# stm32_schematic.net
KiCad netlist of a schematic drawn in Altium Designer
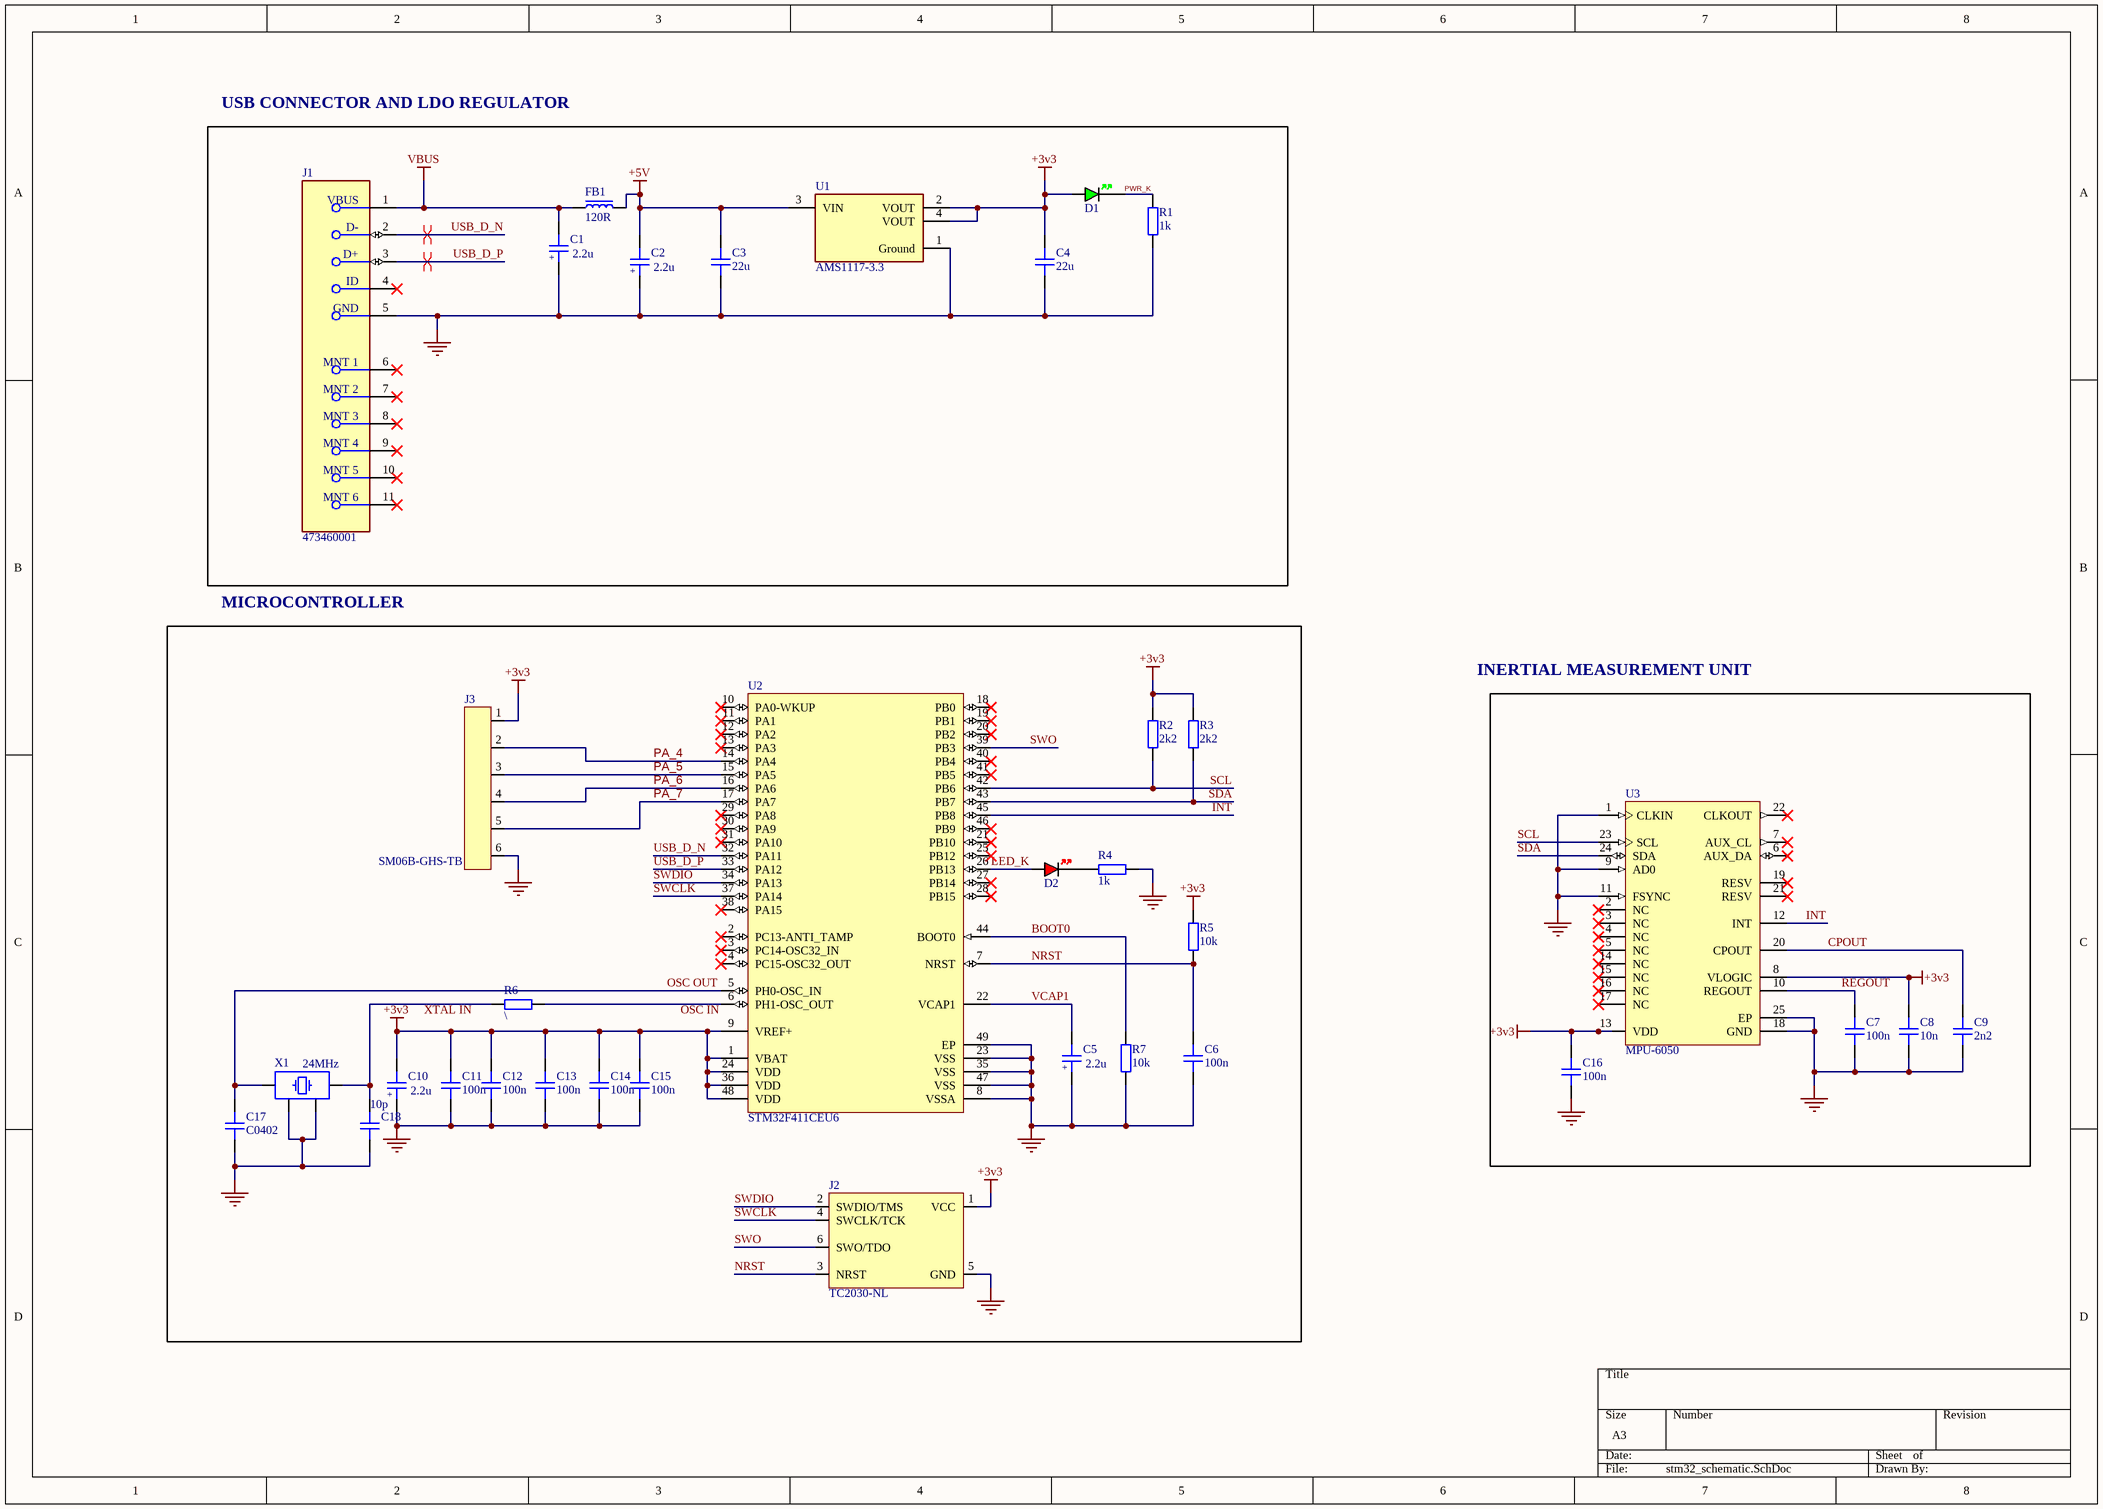
[diagram p0: stm32_schematic.SchDoc]

(export (version "E")
  (design (tool "Eeschema 10.0.6"))
  (components
    (comp (ref "C1")
      (value "2.2u")
      (footprint "CAP_TANT_0603")
      (description "Capacitor SMD Tantalum 0603")
      (libsource (lib "Schematic-Lib-PhilsLab") (part "CAP_TANT_0603"))
    )
    (comp (ref "C2")
      (value "2.2u")
      (footprint "CAP_TANT_0603")
      (description "Capacitor SMD Tantalum 0603")
      (libsource (lib "Schematic-Lib-PhilsLab") (part "CAP_TANT_0603"))
    )
    (comp (ref "C3")
      (value "22u")
      (footprint "CAP_0805")
      (description "Capacitor SMD 0805")
      (libsource (lib "Schematic-Lib-PhilsLab") (part "CAP_0805"))
    )
    (comp (ref "C4")
      (value "22u")
      (footprint "CAP_0805")
      (description "Capacitor SMD 0805")
      (libsource (lib "Schematic-Lib-PhilsLab") (part "CAP_0805"))
    )
    (comp (ref "C5")
      (value "2.2u")
      (footprint "CAP_TANT_0603")
      (description "Capacitor SMD Tantalum 0603")
      (libsource (lib "Schematic-Lib-PhilsLab") (part "CAP_TANT_0603"))
    )
    (comp (ref "C6")
      (value "100n")
      (footprint "CAP_0402")
      (description "Capacitor SMD 0402")
      (libsource (lib "Schematic-Lib-PhilsLab") (part "CAP_0402"))
    )
    (comp (ref "C7")
      (value "100n")
      (footprint "CAP_0402")
      (description "Capacitor SMD 0402")
      (libsource (lib "Schematic-Lib-PhilsLab") (part "CAP_0402"))
    )
    (comp (ref "C8")
      (value "10n")
      (footprint "CAP_0402")
      (description "Capacitor SMD 0402")
      (libsource (lib "Schematic-Lib-PhilsLab") (part "CAP_0402"))
    )
    (comp (ref "C9")
      (value "2n2")
      (footprint "CAP_0402")
      (description "Capacitor SMD 0402")
      (libsource (lib "Schematic-Lib-PhilsLab") (part "CAP_0402"))
    )
    (comp (ref "C10")
      (value "2.2u")
      (footprint "CAP_TANT_0603")
      (description "Capacitor SMD Tantalum 0603")
      (libsource (lib "Schematic-Lib-PhilsLab") (part "CAP_TANT_0603"))
    )
    (comp (ref "C11")
      (value "100n")
      (footprint "CAP_0402")
      (description "Capacitor SMD 0402")
      (libsource (lib "Schematic-Lib-PhilsLab") (part "CAP_0402"))
    )
    (comp (ref "C12")
      (value "100n")
      (footprint "CAP_0402")
      (description "Capacitor SMD 0402")
      (libsource (lib "Schematic-Lib-PhilsLab") (part "CAP_0402"))
    )
    (comp (ref "C13")
      (value "100n")
      (footprint "CAP_0402")
      (description "Capacitor SMD 0402")
      (libsource (lib "Schematic-Lib-PhilsLab") (part "CAP_0402"))
    )
    (comp (ref "C14")
      (value "100n")
      (footprint "CAP_0402")
      (description "Capacitor SMD 0402")
      (libsource (lib "Schematic-Lib-PhilsLab") (part "CAP_0402"))
    )
    (comp (ref "C15")
      (value "100n")
      (footprint "CAP_0402")
      (description "Capacitor SMD 0402")
      (libsource (lib "Schematic-Lib-PhilsLab") (part "CAP_0402"))
    )
    (comp (ref "C16")
      (value "100n")
      (footprint "CAP_0402")
      (description "Capacitor SMD 0402")
      (libsource (lib "Schematic-Lib-PhilsLab") (part "CAP_0402"))
    )
    (comp (ref "C17")
      (value "C0402")
      (footprint "CAP_0402")
      (description "Capacitor SMD 0402")
      (libsource (lib "Schematic-Lib-PhilsLab") (part "CAP_0402"))
    )
    (comp (ref "C18")
      (value "10p")
      (footprint "CAP_0402")
      (description "Capacitor SMD 0402")
      (libsource (lib "Schematic-Lib-PhilsLab") (part "CAP_0402"))
    )
    (comp (ref "D1")
      (value "GREEN")
      (footprint "LED_0402_GREEN")
      (description "LED 0402 GREEN SMD")
      (libsource (lib "Schematic-Lib-PhilsLab") (part "LED_0402_GREEN"))
    )
    (comp (ref "D2")
      (value "RED")
      (footprint "LED_0402_RED")
      (description "LED 0402 RED SMD")
      (libsource (lib "Schematic-Lib-PhilsLab") (part "LED_0402_RED"))
    )
    (comp (ref "FB1")
      (value "120R")
      (footprint "FB_0603")
      (description "Ferrite Bead SMD 0603")
      (libsource (lib "Schematic-Lib-PhilsLab") (part "FB_0603"))
    )
    (comp (ref "J1")
      (value "473460001")
      (footprint "FP-473460001-MFG")
      (description "CONN RCPT USB2.0 MICRO B SMD R/A")
      (fields
        (field (name "OCTOPART") "https://octopart.com/47346-0001-molex-7164928")
        (field (name "MANUFACTURER") "Molex")
      )
      (libsource (lib "Altium Content Vault") (part "53ae1f1d9b557310b43ca686e5bb76a"))
    )
    (comp (ref "J2")
      (value "TC2030-NL")
      (footprint "TC2030-NL-FP")
      (description "Tag-Connect No-Solder SWD Debug Connector (No Legs) DO NOT PLACE")
      (fields
        (field (name "MANUFACTURER") "Tag-Connect")
        (field (name "MANUFACTURER PART NUMBER") "TC2030-NL-FP")
      )
      (libsource (lib "Schematic-Lib-PhilsLab") (part "TC2030-NL"))
    )
    (comp (ref "J3")
      (value "SM06B-GHS-TB")
      (footprint "SM06B-GHS-TB")
      (description "Header Connector 6 Position 1.25MM Pitch SMD Horizontal JST GH")
      (fields (field (name "MANUFACTURER") "JST"))
      (libsource (lib "Schematic-Lib-PhilsLab") (part "SM06B-GHS-TB"))
    )
    (comp (ref "R1")
      (value "1k")
      (footprint "RES_0402")
      (description "Resistor SMD 0402")
      (libsource (lib "Schematic-Lib-PhilsLab") (part "RES_0402"))
    )
    (comp (ref "R2")
      (value "2k2")
      (footprint "RES_0402")
      (description "Resistor SMD 0402")
      (libsource (lib "Schematic-Lib-PhilsLab") (part "RES_0402"))
    )
    (comp (ref "R3")
      (value "2k2")
      (footprint "RES_0402")
      (description "Resistor SMD 0402")
      (libsource (lib "Schematic-Lib-PhilsLab") (part "RES_0402"))
    )
    (comp (ref "R4")
      (value "1k")
      (footprint "RES_0402")
      (description "Resistor SMD 0402")
      (libsource (lib "Schematic-Lib-PhilsLab") (part "RES_0402"))
    )
    (comp (ref "R5")
      (value "10k")
      (footprint "RES_0402")
      (description "Resistor SMD 0402")
      (libsource (lib "Schematic-Lib-PhilsLab") (part "RES_0402"))
    )
    (comp (ref "R6")
      (value "\\")
      (footprint "RES_0402")
      (description "Resistor SMD 0402")
      (libsource (lib "Schematic-Lib-PhilsLab") (part "RES_0402"))
    )
    (comp (ref "R7")
      (value "10k")
      (footprint "RES_0402")
      (description "Resistor SMD 0402")
      (libsource (lib "Schematic-Lib-PhilsLab") (part "RES_0402"))
    )
    (comp (ref "U1")
      (value "AMS1117-3.3")
      (footprint "FP-AMS1117-IPC_C")
      (description "LDO Voltage Regulators 1A, 3.3V")
      (fields
        (field (name "OCTOPART") "https://octopart.com/ams1117-3.3-advanced+monolithic+systems-25899300")
        (field (name "MANUFACTURER") "Advanced Monolithic Systems")
      )
      (libsource (lib "Altium Content Vault") (part "8bdbb5f8e77002000e30dd2845d0354"))
    )
    (comp (ref "U2")
      (value "STM32F411CEU6")
      (footprint "STM-UFQFPN48_L")
      (libsource (lib "Altium Content Vault") (part "MC-ARM-STM32F411-UFQFPN48"))
    )
    (comp (ref "U3")
      (value "MPU-6050")
      (footprint "IS-QFN-24_V")
      (fields (field (name "MANUFACTURER") "InvenSense"))
      (libsource (lib "Altium Content Vault") (part "IS-MPU-6050-QFN-24"))
    )
    (comp (ref "X1")
      (value "24MHz")
      (footprint "XTAL_3225")
      (description "Crystal SMD 24MHz 10PPM 7pF 3225")
      (fields
        (field (name "MANUFACTURER") "Epson")
        (field (name "MANUFACTURER PART NUMBER") "TSX-3225 24.0000MF15X-AC")
      )
      (libsource (lib "Schematic-Lib-PhilsLab") (part "TSX-3225_24.0000MF15X-AC"))
    )
  )
  (nets
    (net (code "1") (name "+3v3") (class "Default")
      (node (ref "C10") (pin "K") (pinfunction "K_K") (pintype "passive"))
      (node (ref "C11") (pin "2") (pinfunction "2_2") (pintype "passive"))
      (node (ref "C12") (pin "2") (pinfunction "2_2") (pintype "passive"))
      (node (ref "C13") (pin "2") (pinfunction "2_2") (pintype "passive"))
      (node (ref "C14") (pin "2") (pinfunction "2_2") (pintype "passive"))
      (node (ref "C15") (pin "2") (pinfunction "2_2") (pintype "passive"))
      (node (ref "C16") (pin "2") (pinfunction "2_2") (pintype "passive"))
      (node (ref "C4") (pin "2") (pinfunction "2_2") (pintype "passive"))
      (node (ref "C8") (pin "1") (pinfunction "1_1") (pintype "passive"))
      (node (ref "D1") (pin "A") (pinfunction "A_A") (pintype "passive"))
      (node (ref "J2") (pin "1") (pinfunction "VCC_1") (pintype "passive"))
      (node (ref "J3") (pin "1") (pinfunction "1_1") (pintype "passive"))
      (node (ref "R2") (pin "2") (pinfunction "2_2") (pintype "passive"))
      (node (ref "R3") (pin "2") (pinfunction "2_2") (pintype "passive"))
      (node (ref "R5") (pin "2") (pinfunction "2_2") (pintype "passive"))
      (node (ref "U1") (pin "2") (pinfunction "VOUT_2") (pintype "passive"))
      (node (ref "U1") (pin "4") (pinfunction "VOUT_4") (pintype "passive"))
      (node (ref "U2") (pin "1") (pinfunction "VBAT_1") (pintype "power_in"))
      (node (ref "U2") (pin "24") (pinfunction "VDD_24") (pintype "power_in"))
      (node (ref "U2") (pin "36") (pinfunction "VDD_36") (pintype "power_in"))
      (node (ref "U2") (pin "48") (pinfunction "VDD_48") (pintype "power_in"))
      (node (ref "U2") (pin "9") (pinfunction "VREF+_9") (pintype "power_in"))
      (node (ref "U3") (pin "13") (pinfunction "VDD_13") (pintype "power_in"))
      (node (ref "U3") (pin "8") (pinfunction "VLOGIC_8") (pintype "power_in"))
    )
    (net (code "2") (name "+5V") (class "Default")
      (node (ref "C2") (pin "K") (pinfunction "K_K") (pintype "passive"))
      (node (ref "C3") (pin "2") (pinfunction "2_2") (pintype "passive"))
      (node (ref "FB1") (pin "2") (pinfunction "2_2") (pintype "passive"))
      (node (ref "U1") (pin "3") (pinfunction "VIN_3") (pintype "power_in"))
    )
    (net (code "3") (name "/BOOT0") (class "Default")
      (node (ref "R7") (pin "2") (pinfunction "2_2") (pintype "passive"))
      (node (ref "U2") (pin "44") (pinfunction "BOOT0_44") (pintype "input"))
    )
    (net (code "4") (name "/CPOUT") (class "Default")
      (node (ref "C9") (pin "1") (pinfunction "1_1") (pintype "passive"))
      (node (ref "U3") (pin "20") (pinfunction "CPOUT_20") (pintype "passive"))
    )
    (net (code "5") (name "/INT") (class "Default")
      (node (ref "U2") (pin "45") (pinfunction "PB8_45") (pintype "bidirectional"))
      (node (ref "U3") (pin "12") (pinfunction "INT_12") (pintype "open_collector"))
    )
    (net (code "6") (name "/LED_K") (class "Default")
      (node (ref "D2") (pin "A") (pinfunction "A_A") (pintype "passive"))
      (node (ref "U2") (pin "26") (pinfunction "PB13_26") (pintype "bidirectional"))
    )
    (net (code "7") (name "/NRST") (class "Default")
      (node (ref "C6") (pin "2") (pinfunction "2_2") (pintype "passive"))
      (node (ref "J2") (pin "3") (pinfunction "NRST_3") (pintype "passive"))
      (node (ref "R5") (pin "1") (pinfunction "1_1") (pintype "passive"))
      (node (ref "U2") (pin "7") (pinfunction "NRST_7") (pintype "bidirectional"))
    )
    (net (code "9") (name "/OSC OUT") (class "Default")
      (node (ref "C17") (pin "2") (pinfunction "2_2") (pintype "passive"))
      (node (ref "U2") (pin "5") (pinfunction "PH0-OSC_IN_5") (pintype "bidirectional"))
      (node (ref "X1") (pin "1") (pinfunction "1_1") (pintype "passive"))
    )
    (net (code "10") (name "/PA_4") (class "Default")
      (node (ref "J3") (pin "2") (pinfunction "2_2") (pintype "passive"))
      (node (ref "U2") (pin "14") (pinfunction "PA4_14") (pintype "bidirectional"))
    )
    (net (code "11") (name "/PA_5") (class "Default")
      (node (ref "J3") (pin "3") (pinfunction "3_3") (pintype "passive"))
      (node (ref "U2") (pin "15") (pinfunction "PA5_15") (pintype "bidirectional"))
    )
    (net (code "12") (name "/PA_6") (class "Default")
      (node (ref "J3") (pin "4") (pinfunction "4_4") (pintype "passive"))
      (node (ref "U2") (pin "16") (pinfunction "PA6_16") (pintype "bidirectional"))
    )
    (net (code "13") (name "/PA_7") (class "Default")
      (node (ref "J3") (pin "5") (pinfunction "5_5") (pintype "passive"))
      (node (ref "U2") (pin "17") (pinfunction "PA7_17") (pintype "bidirectional"))
    )
    (net (code "14") (name "/PWR_K") (class "Default")
      (node (ref "D1") (pin "K") (pinfunction "K_K") (pintype "passive"))
      (node (ref "R1") (pin "2") (pinfunction "2_2") (pintype "passive"))
    )
    (net (code "15") (name "/REGOUT") (class "Default")
      (node (ref "C7") (pin "1") (pinfunction "1_1") (pintype "passive"))
      (node (ref "U3") (pin "10") (pinfunction "REGOUT_10") (pintype "passive"))
    )
    (net (code "16") (name "/SCL") (class "Default")
      (node (ref "R2") (pin "1") (pinfunction "1_1") (pintype "passive"))
      (node (ref "U2") (pin "42") (pinfunction "PB6_42") (pintype "bidirectional"))
      (node (ref "U3") (pin "23") (pinfunction "SCL_23") (pintype "input"))
    )
    (net (code "17") (name "/SDA") (class "Default")
      (node (ref "R3") (pin "1") (pinfunction "1_1") (pintype "passive"))
      (node (ref "U2") (pin "43") (pinfunction "PB7_43") (pintype "bidirectional"))
      (node (ref "U3") (pin "24") (pinfunction "SDA_24") (pintype "bidirectional"))
    )
    (net (code "18") (name "/SWCLK") (class "Default")
      (node (ref "J2") (pin "4") (pinfunction "SWCLK/TCK_4") (pintype "passive"))
      (node (ref "U2") (pin "37") (pinfunction "PA14_37") (pintype "bidirectional"))
    )
    (net (code "19") (name "/SWDIO") (class "Default")
      (node (ref "J2") (pin "2") (pinfunction "SWDIO/TMS_2") (pintype "passive"))
      (node (ref "U2") (pin "34") (pinfunction "PA13_34") (pintype "bidirectional"))
    )
    (net (code "20") (name "/SWO") (class "Default")
      (node (ref "J2") (pin "6") (pinfunction "SWO/TDO_6") (pintype "passive"))
      (node (ref "U2") (pin "39") (pinfunction "PB3_39") (pintype "bidirectional"))
    )
    (net (code "21") (name "/USB_D_N") (class "Default")
      (node (ref "J1") (pin "2") (pinfunction "D-_2") (pintype "bidirectional"))
      (node (ref "U2") (pin "32") (pinfunction "PA11_32") (pintype "bidirectional"))
    )
    (net (code "22") (name "/USB_D_P") (class "Default")
      (node (ref "J1") (pin "3") (pinfunction "D+_3") (pintype "bidirectional"))
      (node (ref "U2") (pin "33") (pinfunction "PA12_33") (pintype "bidirectional"))
    )
    (net (code "23") (name "/VCAP1") (class "Default")
      (node (ref "C5") (pin "K") (pinfunction "K_K") (pintype "passive"))
      (node (ref "U2") (pin "22") (pinfunction "VCAP1_22") (pintype "passive"))
    )
    (net (code "25") (name "GND") (class "Default")
      (node (ref "C1") (pin "A") (pinfunction "A_A") (pintype "passive"))
      (node (ref "C10") (pin "A") (pinfunction "A_A") (pintype "passive"))
      (node (ref "C11") (pin "1") (pinfunction "1_1") (pintype "passive"))
      (node (ref "C12") (pin "1") (pinfunction "1_1") (pintype "passive"))
      (node (ref "C13") (pin "1") (pinfunction "1_1") (pintype "passive"))
      (node (ref "C14") (pin "1") (pinfunction "1_1") (pintype "passive"))
      (node (ref "C15") (pin "1") (pinfunction "1_1") (pintype "passive"))
      (node (ref "C16") (pin "1") (pinfunction "1_1") (pintype "passive"))
      (node (ref "C17") (pin "1") (pinfunction "1_1") (pintype "passive"))
      (node (ref "C18") (pin "1") (pinfunction "1_1") (pintype "passive"))
      (node (ref "C2") (pin "A") (pinfunction "A_A") (pintype "passive"))
      (node (ref "C3") (pin "1") (pinfunction "1_1") (pintype "passive"))
      (node (ref "C4") (pin "1") (pinfunction "1_1") (pintype "passive"))
      (node (ref "C5") (pin "A") (pinfunction "A_A") (pintype "passive"))
      (node (ref "C6") (pin "1") (pinfunction "1_1") (pintype "passive"))
      (node (ref "C7") (pin "2") (pinfunction "2_2") (pintype "passive"))
      (node (ref "C8") (pin "2") (pinfunction "2_2") (pintype "passive"))
      (node (ref "C9") (pin "2") (pinfunction "2_2") (pintype "passive"))
      (node (ref "J1") (pin "5") (pinfunction "GND_5") (pintype "power_in"))
      (node (ref "J2") (pin "5") (pinfunction "GND_5") (pintype "passive"))
      (node (ref "J3") (pin "6") (pinfunction "6_6") (pintype "passive"))
      (node (ref "R1") (pin "1") (pinfunction "1_1") (pintype "passive"))
      (node (ref "R4") (pin "1") (pinfunction "1_1") (pintype "passive"))
      (node (ref "R7") (pin "1") (pinfunction "1_1") (pintype "passive"))
      (node (ref "U1") (pin "1") (pinfunction "Ground_1") (pintype "power_in"))
      (node (ref "U2") (pin "23") (pinfunction "VSS_23") (pintype "power_in"))
      (node (ref "U2") (pin "35") (pinfunction "VSS_35") (pintype "power_in"))
      (node (ref "U2") (pin "47") (pinfunction "VSS_47") (pintype "power_in"))
      (node (ref "U2") (pin "49") (pinfunction "EP_49") (pintype "power_in"))
      (node (ref "U2") (pin "8") (pinfunction "VSSA_8") (pintype "power_in"))
      (node (ref "U3") (pin "1") (pinfunction "CLKIN_1") (pintype "input"))
      (node (ref "U3") (pin "11") (pinfunction "FSYNC_11") (pintype "input"))
      (node (ref "U3") (pin "18") (pinfunction "GND_18") (pintype "power_in"))
      (node (ref "U3") (pin "25") (pinfunction "EP_25") (pintype "power_in"))
      (node (ref "U3") (pin "9") (pinfunction "AD0_9") (pintype "input"))
      (node (ref "X1") (pin "2") (pinfunction "2_2") (pintype "passive"))
      (node (ref "X1") (pin "4") (pinfunction "4_4") (pintype "passive"))
    )
    (net (code "26") (name "Net-(C18-Pad2)") (class "Default")
      (node (ref "C18") (pin "2") (pinfunction "2_2") (pintype "passive"))
      (node (ref "R6") (pin "2") (pinfunction "2_2") (pintype "passive"))
      (node (ref "X1") (pin "3") (pinfunction "3_3") (pintype "passive"))
    )
    (net (code "27") (name "Net-(D2-PadK)") (class "Default")
      (node (ref "D2") (pin "K") (pinfunction "K_K") (pintype "passive"))
      (node (ref "R4") (pin "2") (pinfunction "2_2") (pintype "passive"))
    )
    (net (code "28") (name "Net-(U2-PH1-OSC_OUT)") (class "Default")
      (node (ref "R6") (pin "1") (pinfunction "1_1") (pintype "passive"))
      (node (ref "U2") (pin "6") (pinfunction "PH1-OSC_OUT_6") (pintype "bidirectional"))
    )
    (net (code "29") (name "VBUS") (class "Default")
      (node (ref "C1") (pin "K") (pinfunction "K_K") (pintype "passive"))
      (node (ref "FB1") (pin "1") (pinfunction "1_1") (pintype "passive"))
      (node (ref "J1") (pin "1") (pinfunction "VBUS_1") (pintype "power_in"))
    )
    (net (code "30") (name "unconnected-(J1-ID-Pad4)") (class "Default")
      (node (ref "J1") (pin "4") (pinfunction "ID_4") (pintype "passive+no_connect"))
    )
    (net (code "31") (name "unconnected-(J1-MNT_1-Pad6)") (class "Default")
      (node (ref "J1") (pin "6") (pinfunction "MNT_1_6") (pintype "passive+no_connect"))
    )
    (net (code "32") (name "unconnected-(J1-MNT_2-Pad7)") (class "Default")
      (node (ref "J1") (pin "7") (pinfunction "MNT_2_7") (pintype "passive+no_connect"))
    )
    (net (code "33") (name "unconnected-(J1-MNT_3-Pad8)") (class "Default")
      (node (ref "J1") (pin "8") (pinfunction "MNT_3_8") (pintype "passive+no_connect"))
    )
    (net (code "34") (name "unconnected-(J1-MNT_4-Pad9)") (class "Default")
      (node (ref "J1") (pin "9") (pinfunction "MNT_4_9") (pintype "passive+no_connect"))
    )
    (net (code "35") (name "unconnected-(J1-MNT_5-Pad10)") (class "Default")
      (node (ref "J1") (pin "10") (pinfunction "MNT_5_10") (pintype "passive+no_connect"))
    )
    (net (code "36") (name "unconnected-(J1-MNT_6-Pad11)") (class "Default")
      (node (ref "J1") (pin "11") (pinfunction "MNT_6_11") (pintype "passive+no_connect"))
    )
    (net (code "37") (name "unconnected-(U2-PA0-WKUP-Pad10)") (class "Default")
      (node (ref "U2") (pin "10") (pinfunction "PA0-WKUP_10") (pintype "bidirectional+no_connect"))
    )
    (net (code "38") (name "unconnected-(U2-PA1-Pad11)") (class "Default")
      (node (ref "U2") (pin "11") (pinfunction "PA1_11") (pintype "bidirectional+no_connect"))
    )
    (net (code "39") (name "unconnected-(U2-PA2-Pad12)") (class "Default")
      (node (ref "U2") (pin "12") (pinfunction "PA2_12") (pintype "bidirectional+no_connect"))
    )
    (net (code "40") (name "unconnected-(U2-PA3-Pad13)") (class "Default")
      (node (ref "U2") (pin "13") (pinfunction "PA3_13") (pintype "bidirectional+no_connect"))
    )
    (net (code "41") (name "unconnected-(U2-PA8-Pad29)") (class "Default")
      (node (ref "U2") (pin "29") (pinfunction "PA8_29") (pintype "bidirectional+no_connect"))
    )
    (net (code "42") (name "unconnected-(U2-PA9-Pad30)") (class "Default")
      (node (ref "U2") (pin "30") (pinfunction "PA9_30") (pintype "bidirectional+no_connect"))
    )
    (net (code "43") (name "unconnected-(U2-PA10-Pad31)") (class "Default")
      (node (ref "U2") (pin "31") (pinfunction "PA10_31") (pintype "bidirectional+no_connect"))
    )
    (net (code "44") (name "unconnected-(U2-PA15-Pad38)") (class "Default")
      (node (ref "U2") (pin "38") (pinfunction "PA15_38") (pintype "bidirectional+no_connect"))
    )
    (net (code "45") (name "unconnected-(U2-PB0-Pad18)") (class "Default")
      (node (ref "U2") (pin "18") (pinfunction "PB0_18") (pintype "bidirectional+no_connect"))
    )
    (net (code "46") (name "unconnected-(U2-PB1-Pad19)") (class "Default")
      (node (ref "U2") (pin "19") (pinfunction "PB1_19") (pintype "bidirectional+no_connect"))
    )
    (net (code "47") (name "unconnected-(U2-PB2-Pad20)") (class "Default")
      (node (ref "U2") (pin "20") (pinfunction "PB2_20") (pintype "bidirectional+no_connect"))
    )
    (net (code "48") (name "unconnected-(U2-PB4-Pad40)") (class "Default")
      (node (ref "U2") (pin "40") (pinfunction "PB4_40") (pintype "bidirectional+no_connect"))
    )
    (net (code "49") (name "unconnected-(U2-PB5-Pad41)") (class "Default")
      (node (ref "U2") (pin "41") (pinfunction "PB5_41") (pintype "bidirectional+no_connect"))
    )
    (net (code "50") (name "unconnected-(U2-PB9-Pad46)") (class "Default")
      (node (ref "U2") (pin "46") (pinfunction "PB9_46") (pintype "bidirectional+no_connect"))
    )
    (net (code "51") (name "unconnected-(U2-PB10-Pad21)") (class "Default")
      (node (ref "U2") (pin "21") (pinfunction "PB10_21") (pintype "bidirectional+no_connect"))
    )
    (net (code "52") (name "unconnected-(U2-PB12-Pad25)") (class "Default")
      (node (ref "U2") (pin "25") (pinfunction "PB12_25") (pintype "bidirectional+no_connect"))
    )
    (net (code "53") (name "unconnected-(U2-PB14-Pad27)") (class "Default")
      (node (ref "U2") (pin "27") (pinfunction "PB14_27") (pintype "bidirectional+no_connect"))
    )
    (net (code "54") (name "unconnected-(U2-PB15-Pad28)") (class "Default")
      (node (ref "U2") (pin "28") (pinfunction "PB15_28") (pintype "bidirectional+no_connect"))
    )
    (net (code "55") (name "unconnected-(U2-PC13-ANTI_TAMP-Pad2)") (class "Default")
      (node (ref "U2") (pin "2") (pinfunction "PC13-ANTI_TAMP_2") (pintype "bidirectional+no_connect"))
    )
    (net (code "56") (name "unconnected-(U2-PC14-OSC32_IN-Pad3)") (class "Default")
      (node (ref "U2") (pin "3") (pinfunction "PC14-OSC32_IN_3") (pintype "bidirectional+no_connect"))
    )
    (net (code "57") (name "unconnected-(U2-PC15-OSC32_OUT-Pad4)") (class "Default")
      (node (ref "U2") (pin "4") (pinfunction "PC15-OSC32_OUT_4") (pintype "bidirectional+no_connect"))
    )
    (net (code "58") (name "unconnected-(U3-AUX_CL-Pad7)") (class "Default")
      (node (ref "U3") (pin "7") (pinfunction "AUX_CL_7") (pintype "output+no_connect"))
    )
    (net (code "59") (name "unconnected-(U3-AUX_DA-Pad6)") (class "Default")
      (node (ref "U3") (pin "6") (pinfunction "AUX_DA_6") (pintype "bidirectional+no_connect"))
    )
    (net (code "60") (name "unconnected-(U3-CLKOUT-Pad22)") (class "Default")
      (node (ref "U3") (pin "22") (pinfunction "CLKOUT_22") (pintype "output+no_connect"))
    )
    (net (code "61") (name "unconnected-(U3-NC-Pad2)") (class "Default")
      (node (ref "U3") (pin "2") (pinfunction "NC_2") (pintype "passive+no_connect"))
    )
    (net (code "62") (name "unconnected-(U3-NC-Pad3)") (class "Default")
      (node (ref "U3") (pin "3") (pinfunction "NC_3") (pintype "passive+no_connect"))
    )
    (net (code "63") (name "unconnected-(U3-NC-Pad4)") (class "Default")
      (node (ref "U3") (pin "4") (pinfunction "NC_4") (pintype "passive+no_connect"))
    )
    (net (code "64") (name "unconnected-(U3-NC-Pad5)") (class "Default")
      (node (ref "U3") (pin "5") (pinfunction "NC_5") (pintype "passive+no_connect"))
    )
    (net (code "65") (name "unconnected-(U3-NC-Pad14)") (class "Default")
      (node (ref "U3") (pin "14") (pinfunction "NC_14") (pintype "passive+no_connect"))
    )
    (net (code "66") (name "unconnected-(U3-NC-Pad15)") (class "Default")
      (node (ref "U3") (pin "15") (pinfunction "NC_15") (pintype "passive+no_connect"))
    )
    (net (code "67") (name "unconnected-(U3-NC-Pad16)") (class "Default")
      (node (ref "U3") (pin "16") (pinfunction "NC_16") (pintype "passive+no_connect"))
    )
    (net (code "68") (name "unconnected-(U3-NC-Pad17)") (class "Default")
      (node (ref "U3") (pin "17") (pinfunction "NC_17") (pintype "passive+no_connect"))
    )
    (net (code "69") (name "unconnected-(U3-RESV-Pad19)") (class "Default")
      (node (ref "U3") (pin "19") (pinfunction "RESV_19") (pintype "passive+no_connect"))
    )
    (net (code "70") (name "unconnected-(U3-RESV-Pad21)") (class "Default")
      (node (ref "U3") (pin "21") (pinfunction "RESV_21") (pintype "passive+no_connect"))
    )
  )
)
